# power_filter.net
KiCad netlist of a schematic drawn in Altium Designer
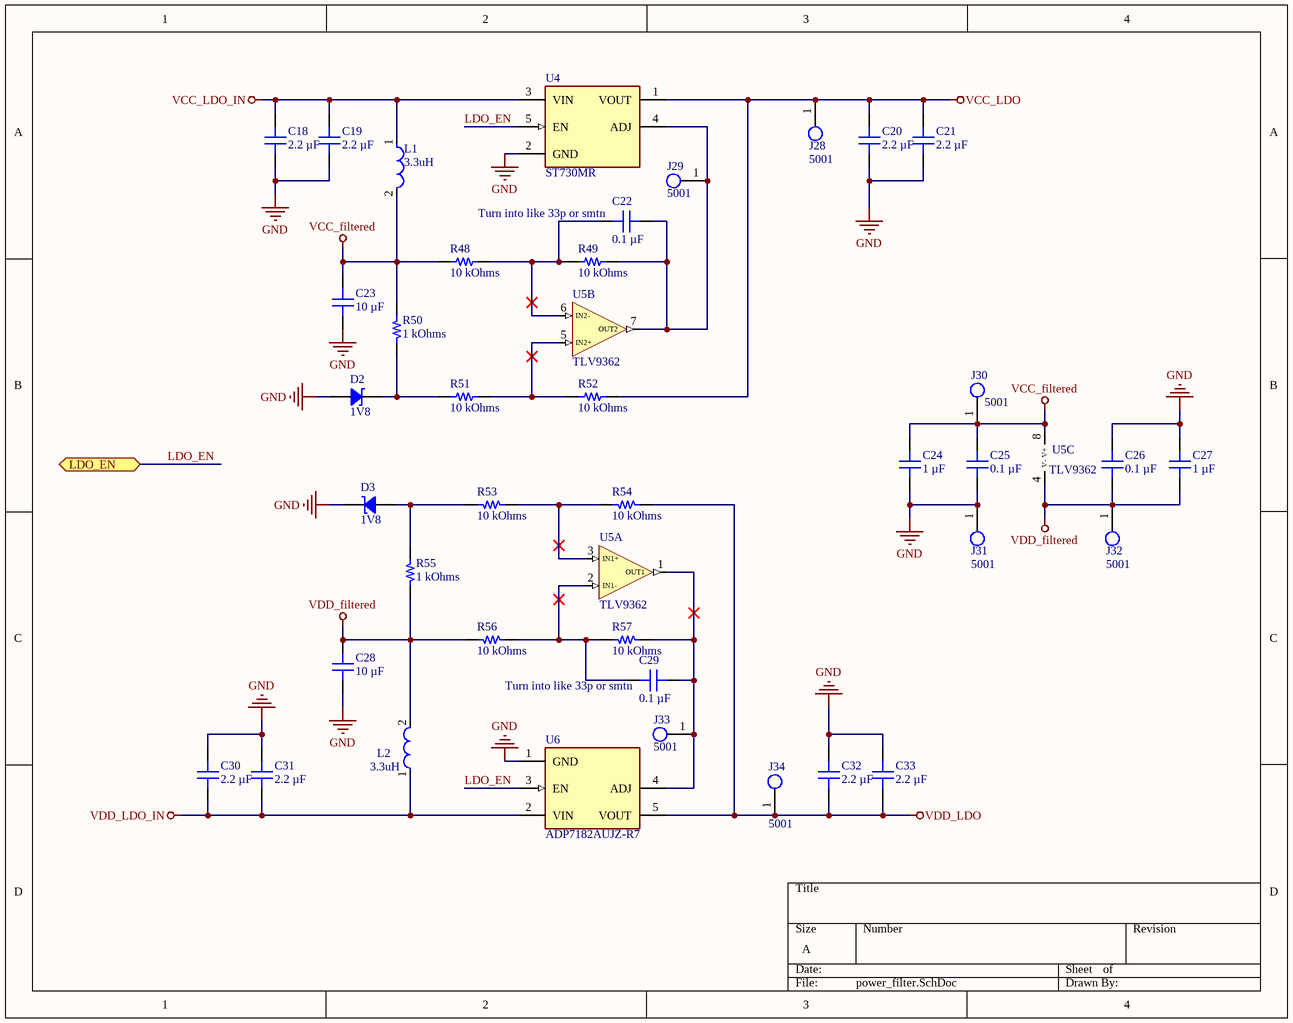
[diagram p0: power_filter.SchDoc]

(export (version "E")
  (design (tool "Eeschema 10.0.6"))
  (components
    (comp (ref "C18")
      (value "2.2 µF")
      (footprint "CAP 1206_3216 - 0.8MM")
      (description "CAP CER 2.2UF 25V X7R 1206")
      (fields
        (field (name "PART NUMBER") "885382208001")
        (field (name "CAPACITANCE") "2.2 µF")
        (field (name "MANUFACTURER") "Würth Elektronik")
      )
      (libsource (lib "Celestial Altium Library - altium_library") (part "Capacitor"))
    )
    (comp (ref "C19")
      (value "2.2 µF")
      (footprint "CAP 1206_3216 - 0.8MM")
      (description "CAP CER 2.2UF 25V X7R 1206")
      (fields
        (field (name "PART NUMBER") "885382208001")
        (field (name "CAPACITANCE") "2.2 µF")
        (field (name "MANUFACTURER") "Würth Elektronik")
      )
      (libsource (lib "Celestial Altium Library - altium_library") (part "Capacitor"))
    )
    (comp (ref "C20")
      (value "2.2 µF")
      (footprint "CAP 1206_3216 - 0.8MM")
      (description "CAP CER 2.2UF 25V X7R 1206")
      (fields
        (field (name "PART NUMBER") "885382208001")
        (field (name "CAPACITANCE") "2.2 µF")
        (field (name "MANUFACTURER") "Würth Elektronik")
      )
      (libsource (lib "Celestial Altium Library - altium_library") (part "Capacitor"))
    )
    (comp (ref "C21")
      (value "2.2 µF")
      (footprint "CAP 1206_3216 - 0.8MM")
      (description "CAP CER 2.2UF 25V X7R 1206")
      (fields
        (field (name "PART NUMBER") "885382208001")
        (field (name "CAPACITANCE") "2.2 µF")
        (field (name "MANUFACTURER") "Würth Elektronik")
      )
      (libsource (lib "Celestial Altium Library - altium_library") (part "Capacitor"))
    )
    (comp (ref "C22")
      (value "0.1 µF")
      (footprint "CAP 1206_3216 - 0.8MM")
      (description "CAP CER 0.1UF 50V X7R 1206")
      (fields
        (field (name "PART NUMBER") "885012208087")
        (field (name "CAPACITANCE") "0.1 µF")
        (field (name "MANUFACTURER") "Würth Elektronik")
      )
      (libsource (lib "Celestial Altium Library - altium_library") (part "Capacitor"))
    )
    (comp (ref "C23")
      (value "10 µF")
      (footprint "CAP 1206_3216 - 0.8MM")
      (description "CAP CER 10UF 25V X7R 1206")
      (fields
        (field (name "PART NUMBER") "885012208069")
        (field (name "CAPACITANCE") "10 µF")
        (field (name "MANUFACTURER") "Würth Elektronik")
      )
      (libsource (lib "Celestial Altium Library - altium_library") (part "Capacitor"))
    )
    (comp (ref "C24")
      (value "1 µF")
      (footprint "CAP 1206_3216 - 0.8MM")
      (description "CAP CER 1UF 50V X7R 1206")
      (fields
        (field (name "PART NUMBER") "885012208093")
        (field (name "CAPACITANCE") "1 µF")
        (field (name "MANUFACTURER") "Würth Elektronik")
      )
      (libsource (lib "Celestial Altium Library - altium_library") (part "Capacitor"))
    )
    (comp (ref "C25")
      (value "0.1 µF")
      (footprint "CAP 1206_3216 - 0.8MM")
      (description "CAP CER 0.1UF 50V X7R 1206")
      (fields
        (field (name "PART NUMBER") "885012208087")
        (field (name "CAPACITANCE") "0.1 µF")
        (field (name "MANUFACTURER") "Würth Elektronik")
      )
      (libsource (lib "Celestial Altium Library - altium_library") (part "Capacitor"))
    )
    (comp (ref "C26")
      (value "0.1 µF")
      (footprint "CAP 1206_3216 - 0.8MM")
      (description "CAP CER 0.1UF 50V X7R 1206")
      (fields
        (field (name "PART NUMBER") "885012208087")
        (field (name "CAPACITANCE") "0.1 µF")
        (field (name "MANUFACTURER") "Würth Elektronik")
      )
      (libsource (lib "Celestial Altium Library - altium_library") (part "Capacitor"))
    )
    (comp (ref "C27")
      (value "1 µF")
      (footprint "CAP 1206_3216 - 0.8MM")
      (description "CAP CER 1UF 50V X7R 1206")
      (fields
        (field (name "PART NUMBER") "885012208093")
        (field (name "CAPACITANCE") "1 µF")
        (field (name "MANUFACTURER") "Würth Elektronik")
      )
      (libsource (lib "Celestial Altium Library - altium_library") (part "Capacitor"))
    )
    (comp (ref "C28")
      (value "10 µF")
      (footprint "CAP 1206_3216 - 0.8MM")
      (description "CAP CER 10UF 25V X7R 1206")
      (fields
        (field (name "PART NUMBER") "885012208069")
        (field (name "CAPACITANCE") "10 µF")
        (field (name "MANUFACTURER") "Würth Elektronik")
      )
      (libsource (lib "Celestial Altium Library - altium_library") (part "Capacitor"))
    )
    (comp (ref "C29")
      (value "0.1 µF")
      (footprint "CAP 1206_3216 - 0.8MM")
      (description "CAP CER 0.1UF 50V X7R 1206")
      (fields
        (field (name "PART NUMBER") "885012208087")
        (field (name "CAPACITANCE") "0.1 µF")
        (field (name "MANUFACTURER") "Würth Elektronik")
      )
      (libsource (lib "Celestial Altium Library - altium_library") (part "Capacitor"))
    )
    (comp (ref "C30")
      (value "2.2 µF")
      (footprint "CAP 1206_3216 - 0.8MM")
      (description "CAP CER 2.2UF 25V X7R 1206")
      (fields
        (field (name "PART NUMBER") "885382208001")
        (field (name "CAPACITANCE") "2.2 µF")
        (field (name "MANUFACTURER") "Würth Elektronik")
      )
      (libsource (lib "Celestial Altium Library - altium_library") (part "Capacitor"))
    )
    (comp (ref "C31")
      (value "2.2 µF")
      (footprint "CAP 1206_3216 - 0.8MM")
      (description "CAP CER 2.2UF 25V X7R 1206")
      (fields
        (field (name "PART NUMBER") "885382208001")
        (field (name "CAPACITANCE") "2.2 µF")
        (field (name "MANUFACTURER") "Würth Elektronik")
      )
      (libsource (lib "Celestial Altium Library - altium_library") (part "Capacitor"))
    )
    (comp (ref "C32")
      (value "2.2 µF")
      (footprint "CAP 1206_3216 - 0.8MM")
      (description "CAP CER 2.2UF 25V X7R 1206")
      (fields
        (field (name "PART NUMBER") "885382208001")
        (field (name "CAPACITANCE") "2.2 µF")
        (field (name "MANUFACTURER") "Würth Elektronik")
      )
      (libsource (lib "Celestial Altium Library - altium_library") (part "Capacitor"))
    )
    (comp (ref "C33")
      (value "2.2 µF")
      (footprint "CAP 1206_3216 - 0.8MM")
      (description "CAP CER 2.2UF 25V X7R 1206")
      (fields
        (field (name "PART NUMBER") "885382208001")
        (field (name "CAPACITANCE") "2.2 µF")
        (field (name "MANUFACTURER") "Würth Elektronik")
      )
      (libsource (lib "Celestial Altium Library - altium_library") (part "Capacitor"))
    )
    (comp (ref "D2") (value "1V8") (footprint "SOD323") (libsource (lib "za_koncar") (part "BZX38450-C1V8X")))
    (comp (ref "D3") (value "1V8") (footprint "SOD323") (libsource (lib "za_koncar") (part "BZX38450-C1V8X")))
    (comp (ref "J28")
      (value "5001")
      (footprint "FP-5001-MFG")
      (description "PC TEST POINT MINIATURE BLACK")
      (libsource (lib "za_koncar") (part "CMP-2000-05181-2"))
    )
    (comp (ref "J29")
      (value "5001")
      (footprint "FP-5001-MFG")
      (description "PC TEST POINT MINIATURE BLACK")
      (libsource (lib "za_koncar") (part "CMP-2000-05181-2"))
    )
    (comp (ref "J30")
      (value "5001")
      (footprint "FP-5001-MFG")
      (description "PC TEST POINT MINIATURE BLACK")
      (libsource (lib "za_koncar") (part "CMP-2000-05181-2"))
    )
    (comp (ref "J31")
      (value "5001")
      (footprint "FP-5001-MFG")
      (description "PC TEST POINT MINIATURE BLACK")
      (libsource (lib "za_koncar") (part "CMP-2000-05181-2"))
    )
    (comp (ref "J32")
      (value "5001")
      (footprint "FP-5001-MFG")
      (description "PC TEST POINT MINIATURE BLACK")
      (libsource (lib "za_koncar") (part "CMP-2000-05181-2"))
    )
    (comp (ref "J33")
      (value "5001")
      (footprint "FP-5001-MFG")
      (description "PC TEST POINT MINIATURE BLACK")
      (libsource (lib "za_koncar") (part "CMP-2000-05181-2"))
    )
    (comp (ref "J34")
      (value "5001")
      (footprint "FP-5001-MFG")
      (description "PC TEST POINT MINIATURE BLACK")
      (libsource (lib "za_koncar") (part "CMP-2000-05181-2"))
    )
    (comp (ref "L1")
      (value "3.3uH")
      (footprint "FP-MLZ2012-1_25-IPC_B")
      (description "Shielded Multilayer Inductor 3.3uH ±20% 500mA 260mΩ SMD 0805")
      (fields (field (name "TOLERANCE") "20%"))
      (libsource (lib "za_koncar") (part "MLZ2012M"))
    )
    (comp (ref "L2")
      (value "3.3uH")
      (footprint "FP-MLZ2012-1_25-IPC_B")
      (description "Shielded Multilayer Inductor 3.3uH ±20% 500mA 260mΩ SMD 0805")
      (fields (field (name "TOLERANCE") "20%"))
      (libsource (lib "za_koncar") (part "MLZ2012M"))
    )
    (comp (ref "R48")
      (value "10 kOhms")
      (footprint "YAGEO RES 1206_3216")
      (description "RES SMD 10K OHM 1% 1/4W 1206")
      (fields (field (name "PART NUMBER") "RT1206FRE0710KL") (field (name "MANUFACTURER") "Yageo"))
      (libsource (lib "Celestial Altium Library - altium_library") (part "Resistor"))
    )
    (comp (ref "R49")
      (value "10 kOhms")
      (footprint "YAGEO RES 1206_3216")
      (description "RES SMD 10K OHM 1% 1/4W 1206")
      (fields (field (name "PART NUMBER") "RT1206FRE0710KL") (field (name "MANUFACTURER") "Yageo"))
      (libsource (lib "Celestial Altium Library - altium_library") (part "Resistor"))
    )
    (comp (ref "R50")
      (value "1 kOhms")
      (footprint "YAGEO RES 1206_3216")
      (description "RES SMD 1K OHM 1% 1/4W 1206")
      (fields (field (name "PART NUMBER") "RT1206FRE071KL") (field (name "MANUFACTURER") "Yageo"))
      (libsource (lib "Celestial Altium Library - altium_library") (part "Resistor"))
    )
    (comp (ref "R51")
      (value "10 kOhms")
      (footprint "YAGEO RES 1206_3216")
      (description "RES SMD 10K OHM 1% 1/4W 1206")
      (fields (field (name "PART NUMBER") "RT1206FRE0710KL") (field (name "MANUFACTURER") "Yageo"))
      (libsource (lib "Celestial Altium Library - altium_library") (part "Resistor"))
    )
    (comp (ref "R52")
      (value "10 kOhms")
      (footprint "YAGEO RES 1206_3216")
      (description "RES SMD 10K OHM 1% 1/4W 1206")
      (fields (field (name "PART NUMBER") "RT1206FRE0710KL") (field (name "MANUFACTURER") "Yageo"))
      (libsource (lib "Celestial Altium Library - altium_library") (part "Resistor"))
    )
    (comp (ref "R53")
      (value "10 kOhms")
      (footprint "YAGEO RES 1206_3216")
      (description "RES SMD 10K OHM 1% 1/4W 1206")
      (fields (field (name "PART NUMBER") "RT1206FRE0710KL") (field (name "MANUFACTURER") "Yageo"))
      (libsource (lib "Celestial Altium Library - altium_library") (part "Resistor"))
    )
    (comp (ref "R54")
      (value "10 kOhms")
      (footprint "YAGEO RES 1206_3216")
      (description "RES SMD 10K OHM 1% 1/4W 1206")
      (fields (field (name "PART NUMBER") "RT1206FRE0710KL") (field (name "MANUFACTURER") "Yageo"))
      (libsource (lib "Celestial Altium Library - altium_library") (part "Resistor"))
    )
    (comp (ref "R55")
      (value "1 kOhms")
      (footprint "YAGEO RES 1206_3216")
      (description "RES SMD 1K OHM 1% 1/4W 1206")
      (fields (field (name "PART NUMBER") "RT1206FRE071KL") (field (name "MANUFACTURER") "Yageo"))
      (libsource (lib "Celestial Altium Library - altium_library") (part "Resistor"))
    )
    (comp (ref "R56")
      (value "10 kOhms")
      (footprint "YAGEO RES 1206_3216")
      (description "RES SMD 10K OHM 1% 1/4W 1206")
      (fields (field (name "PART NUMBER") "RT1206FRE0710KL") (field (name "MANUFACTURER") "Yageo"))
      (libsource (lib "Celestial Altium Library - altium_library") (part "Resistor"))
    )
    (comp (ref "R57")
      (value "10 kOhms")
      (footprint "YAGEO RES 1206_3216")
      (description "RES SMD 10K OHM 1% 1/4W 1206")
      (fields (field (name "PART NUMBER") "RT1206FRE0710KL") (field (name "MANUFACTURER") "Yageo"))
      (libsource (lib "Celestial Altium Library - altium_library") (part "Resistor"))
    )
    (comp (ref "U4")
      (value "ST730MR")
      (footprint "FP-UJ-5-IPC_B")
      (libsource (lib "za_koncar") (part "ST730MR"))
    )
    (comp (ref "U5")
      (value "TLV9362")
      (footprint "za_koncar:SOIC8-127P600X175-8N")
      (description "TLV936x 10-MHz, 40-V, RRO, Operational Amplifie")
      (libsource (lib "za_koncar") (part "TLV9362"))
    )
    (comp (ref "U6")
      (value "ADP7182AUJZ-R7")
      (footprint "FP-UJ-5-IPC_B")
      (description "IC REG LIN NEG ADJ 200MA 5TSOT")
      (fields
        (field (name "MANUFACTURER") "Analog Devices")
        (field (name "OCTOPART") "https://octopart.com/adp7182aujz-r7-analog+devices-21054665")
      )
      (libsource (lib "za_koncar") (part "ADP7182"))
    )
  )
  (nets
    (net (code "1") (name "/LDO_EN") (class "Default")
      (node (ref "U4") (pin "5") (pinfunction "EN_5") (pintype "input"))
      (node (ref "U6") (pin "3") (pinfunction "EN_3") (pintype "input"))
    )
    (net (code "2") (name "GND") (class "Default")
      (node (ref "C18") (pin "1") (pinfunction "1_1") (pintype "passive"))
      (node (ref "C19") (pin "1") (pinfunction "1_1") (pintype "passive"))
      (node (ref "C20") (pin "1") (pinfunction "1_1") (pintype "passive"))
      (node (ref "C21") (pin "1") (pinfunction "1_1") (pintype "passive"))
      (node (ref "C23") (pin "1") (pinfunction "1_1") (pintype "passive"))
      (node (ref "C24") (pin "1") (pinfunction "1_1") (pintype "passive"))
      (node (ref "C25") (pin "1") (pinfunction "1_1") (pintype "passive"))
      (node (ref "C26") (pin "2") (pinfunction "2_2") (pintype "passive"))
      (node (ref "C27") (pin "2") (pinfunction "2_2") (pintype "passive"))
      (node (ref "C28") (pin "1") (pinfunction "1_1") (pintype "passive"))
      (node (ref "C30") (pin "1") (pinfunction "1_1") (pintype "passive"))
      (node (ref "C31") (pin "1") (pinfunction "1_1") (pintype "passive"))
      (node (ref "C32") (pin "1") (pinfunction "1_1") (pintype "passive"))
      (node (ref "C33") (pin "1") (pinfunction "1_1") (pintype "passive"))
      (node (ref "D2") (pin "1") (pinfunction "1_1") (pintype "passive"))
      (node (ref "D3") (pin "2") (pinfunction "2_2") (pintype "passive"))
      (node (ref "J31") (pin "1") (pinfunction "1_1") (pintype "passive"))
      (node (ref "U4") (pin "2") (pinfunction "GND_2") (pintype "power_in"))
      (node (ref "U6") (pin "1") (pinfunction "GND_1") (pintype "power_in"))
    )
    (net (code "3") (name "Net-(D2-Pad2)") (class "Default")
      (node (ref "D2") (pin "2") (pinfunction "2_2") (pintype "passive"))
      (node (ref "R50") (pin "2") (pinfunction "2_2") (pintype "passive"))
      (node (ref "R51") (pin "2") (pinfunction "2_2") (pintype "passive"))
    )
    (net (code "4") (name "Net-(D3-Pad1)") (class "Default")
      (node (ref "D3") (pin "1") (pinfunction "1_1") (pintype "passive"))
      (node (ref "R53") (pin "2") (pinfunction "2_2") (pintype "passive"))
      (node (ref "R55") (pin "1") (pinfunction "1_1") (pintype "passive"))
    )
    (net (code "5") (name "Net-(U4-ADJ)") (class "Default")
      (node (ref "C22") (pin "1") (pinfunction "1_1") (pintype "passive"))
      (node (ref "J29") (pin "1") (pinfunction "1_1") (pintype "passive"))
      (node (ref "R49") (pin "1") (pinfunction "1_1") (pintype "passive"))
      (node (ref "U4") (pin "4") (pinfunction "ADJ_4") (pintype "passive"))
      (node (ref "U5") (pin "7") (pinfunction "OUT2_7") (pintype "output"))
    )
    (net (code "6") (name "Net-(U5A-IN1+)") (class "Default")
      (node (ref "R53") (pin "1") (pinfunction "1_1") (pintype "passive"))
      (node (ref "R54") (pin "2") (pinfunction "2_2") (pintype "passive"))
      (node (ref "U5") (pin "3") (pinfunction "IN1+_3") (pintype "input"))
    )
    (net (code "7") (name "Net-(U5A-IN1-)") (class "Default")
      (node (ref "C29") (pin "1") (pinfunction "1_1") (pintype "passive"))
      (node (ref "R56") (pin "1") (pinfunction "1_1") (pintype "passive"))
      (node (ref "R57") (pin "2") (pinfunction "2_2") (pintype "passive"))
      (node (ref "U5") (pin "2") (pinfunction "IN1-_2") (pintype "input"))
    )
    (net (code "8") (name "Net-(U5A-OUT1)") (class "Default")
      (node (ref "C29") (pin "2") (pinfunction "2_2") (pintype "passive"))
      (node (ref "J33") (pin "1") (pinfunction "1_1") (pintype "passive"))
      (node (ref "R57") (pin "1") (pinfunction "1_1") (pintype "passive"))
      (node (ref "U5") (pin "1") (pinfunction "OUT1_1") (pintype "output"))
      (node (ref "U6") (pin "4") (pinfunction "ADJ_4") (pintype "passive"))
    )
    (net (code "9") (name "Net-(U5B-IN2+)") (class "Default")
      (node (ref "R51") (pin "1") (pinfunction "1_1") (pintype "passive"))
      (node (ref "R52") (pin "2") (pinfunction "2_2") (pintype "passive"))
      (node (ref "U5") (pin "5") (pinfunction "IN2+_5") (pintype "input"))
    )
    (net (code "10") (name "Net-(U5B-IN2-)") (class "Default")
      (node (ref "C22") (pin "2") (pinfunction "2_2") (pintype "passive"))
      (node (ref "R48") (pin "1") (pinfunction "1_1") (pintype "passive"))
      (node (ref "R49") (pin "2") (pinfunction "2_2") (pintype "passive"))
      (node (ref "U5") (pin "6") (pinfunction "IN2-_6") (pintype "input"))
    )
    (net (code "11") (name "VCC_LDO") (class "Default")
      (node (ref "C20") (pin "2") (pinfunction "2_2") (pintype "passive"))
      (node (ref "C21") (pin "2") (pinfunction "2_2") (pintype "passive"))
      (node (ref "J28") (pin "1") (pinfunction "1_1") (pintype "passive"))
      (node (ref "R52") (pin "1") (pinfunction "1_1") (pintype "passive"))
      (node (ref "U4") (pin "1") (pinfunction "VOUT_1") (pintype "power_in"))
    )
    (net (code "12") (name "VCC_LDO_IN") (class "Default")
      (node (ref "C18") (pin "2") (pinfunction "2_2") (pintype "passive"))
      (node (ref "C19") (pin "2") (pinfunction "2_2") (pintype "passive"))
      (node (ref "L1") (pin "1") (pinfunction "1_1") (pintype "passive"))
      (node (ref "U4") (pin "3") (pinfunction "VIN_3") (pintype "power_in"))
    )
    (net (code "13") (name "VCC_filtered") (class "Default")
      (node (ref "C23") (pin "2") (pinfunction "2_2") (pintype "passive"))
      (node (ref "C24") (pin "2") (pinfunction "2_2") (pintype "passive"))
      (node (ref "C25") (pin "2") (pinfunction "2_2") (pintype "passive"))
      (node (ref "J30") (pin "1") (pinfunction "1_1") (pintype "passive"))
      (node (ref "L1") (pin "2") (pinfunction "2_2") (pintype "passive"))
      (node (ref "R48") (pin "2") (pinfunction "2_2") (pintype "passive"))
      (node (ref "R50") (pin "1") (pinfunction "1_1") (pintype "passive"))
      (node (ref "U5") (pin "8") (pinfunction "V+_8") (pintype "power_in"))
    )
    (net (code "14") (name "VDD_LDO") (class "Default")
      (node (ref "C32") (pin "2") (pinfunction "2_2") (pintype "passive"))
      (node (ref "C33") (pin "2") (pinfunction "2_2") (pintype "passive"))
      (node (ref "J34") (pin "1") (pinfunction "1_1") (pintype "passive"))
      (node (ref "R54") (pin "1") (pinfunction "1_1") (pintype "passive"))
      (node (ref "U6") (pin "5") (pinfunction "VOUT_5") (pintype "power_in"))
    )
    (net (code "15") (name "VDD_LDO_IN") (class "Default")
      (node (ref "C30") (pin "2") (pinfunction "2_2") (pintype "passive"))
      (node (ref "C31") (pin "2") (pinfunction "2_2") (pintype "passive"))
      (node (ref "L2") (pin "1") (pinfunction "1_1") (pintype "passive"))
      (node (ref "U6") (pin "2") (pinfunction "VIN_2") (pintype "power_in"))
    )
    (net (code "16") (name "VDD_filtered") (class "Default")
      (node (ref "C26") (pin "1") (pinfunction "1_1") (pintype "passive"))
      (node (ref "C27") (pin "1") (pinfunction "1_1") (pintype "passive"))
      (node (ref "C28") (pin "2") (pinfunction "2_2") (pintype "passive"))
      (node (ref "J32") (pin "1") (pinfunction "1_1") (pintype "passive"))
      (node (ref "L2") (pin "2") (pinfunction "2_2") (pintype "passive"))
      (node (ref "R55") (pin "2") (pinfunction "2_2") (pintype "passive"))
      (node (ref "R56") (pin "2") (pinfunction "2_2") (pintype "passive"))
      (node (ref "U5") (pin "4") (pinfunction "V-_4") (pintype "power_in"))
    )
  )
)
